# Sheet1.net
KiCad netlist of a schematic drawn in Altium Designer
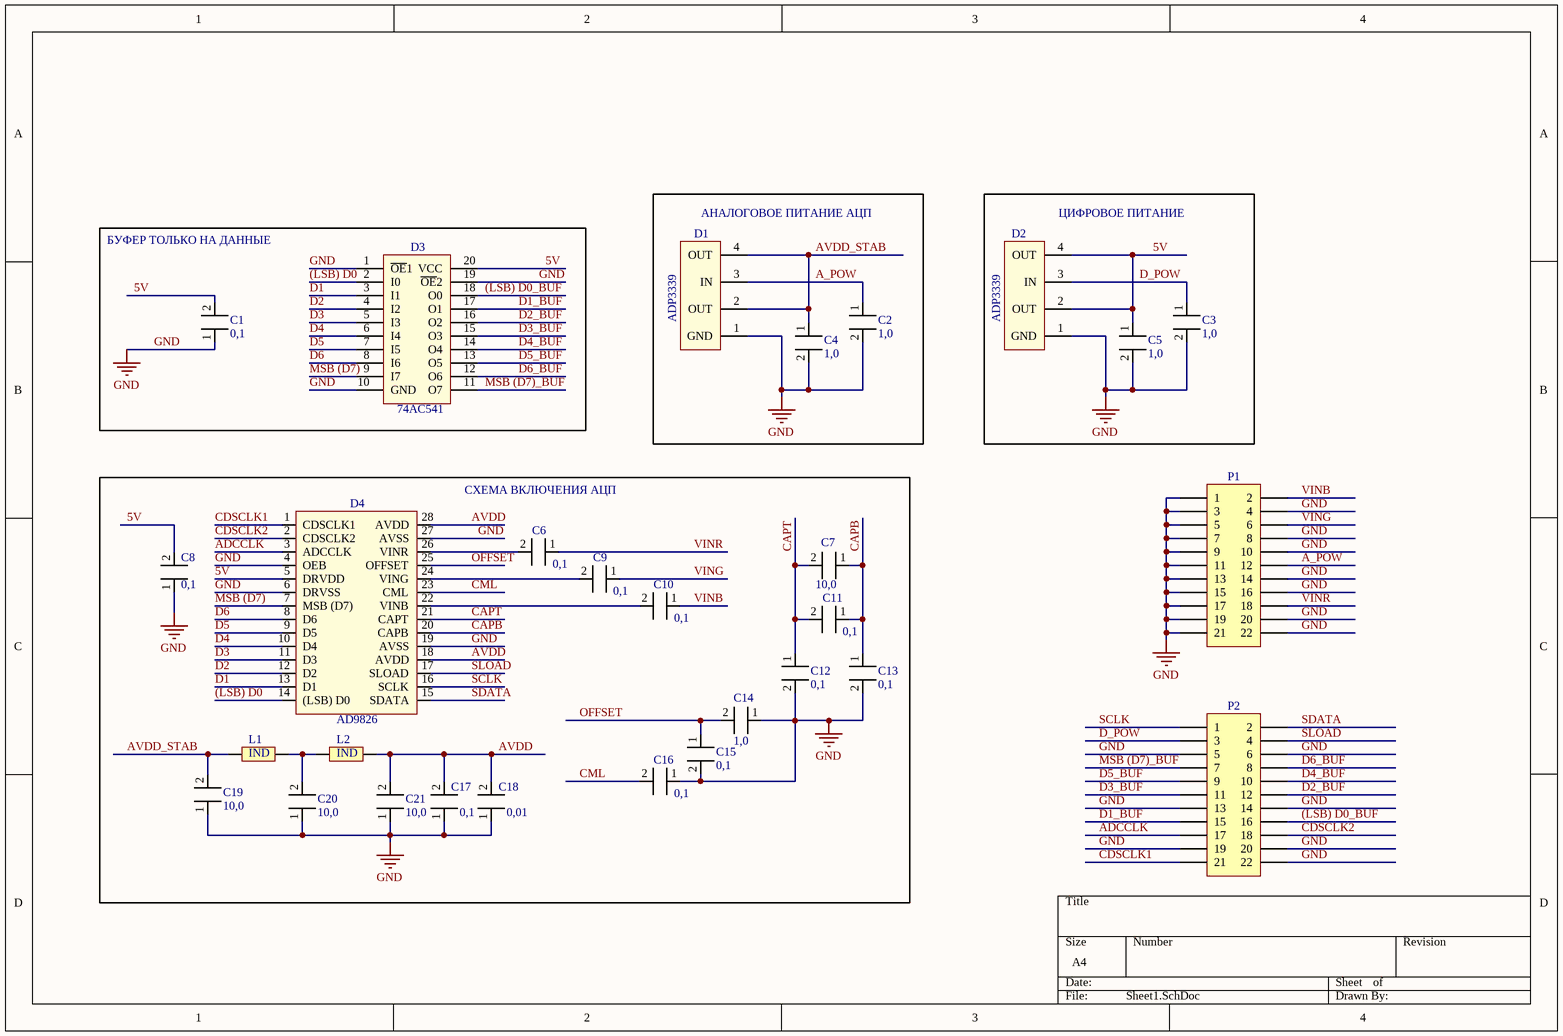
[diagram p0: Sheet1.SchDoc]

(export (version "E")
  (design (tool "Eeschema 10.0.6"))
  (components
    (comp (ref "C1") (value "0,1") (footprint "CAP_SMALL") (libsource (lib "Schlib") (part "CAP_SMALL")))
    (comp (ref "C2") (value "1,0") (footprint "CAP_SMALL") (libsource (lib "Schlib") (part "CAP_SMALL")))
    (comp (ref "C3") (value "1,0") (footprint "CAP_SMALL") (libsource (lib "Schlib") (part "CAP_SMALL")))
    (comp (ref "C4") (value "1,0") (footprint "CAP_SMALL") (libsource (lib "Schlib") (part "CAP_SMALL")))
    (comp (ref "C5") (value "1,0") (footprint "CAP_SMALL") (libsource (lib "Schlib") (part "CAP_SMALL")))
    (comp (ref "C6") (value "0,1") (footprint "CAP_SMALL") (libsource (lib "Schlib") (part "CAP_SMALL")))
    (comp (ref "C7") (value "10,0") (footprint "Cap_BIG") (libsource (lib "Schlib") (part "CAP_SMALL")))
    (comp (ref "C8") (value "0,1") (footprint "CAP_SMALL") (libsource (lib "Schlib") (part "CAP_SMALL")))
    (comp (ref "C9") (value "0,1") (footprint "CAP_SMALL") (libsource (lib "Schlib") (part "CAP_SMALL")))
    (comp (ref "C10") (value "0,1") (footprint "CAP_SMALL") (libsource (lib "Schlib") (part "CAP_SMALL")))
    (comp (ref "C11") (value "0,1") (footprint "CAP_SMALL") (libsource (lib "Schlib") (part "CAP_SMALL")))
    (comp (ref "C12") (value "0,1") (footprint "CAP_SMALL") (libsource (lib "Schlib") (part "CAP_SMALL")))
    (comp (ref "C13") (value "0,1") (footprint "CAP_SMALL") (libsource (lib "Schlib") (part "CAP_SMALL")))
    (comp (ref "C14") (value "1,0") (footprint "CAP_SMALL") (libsource (lib "Schlib") (part "CAP_SMALL")))
    (comp (ref "C15") (value "0,1") (footprint "CAP_SMALL") (libsource (lib "Schlib") (part "CAP_SMALL")))
    (comp (ref "C16") (value "0,1") (footprint "CAP_SMALL") (libsource (lib "Schlib") (part "CAP_SMALL")))
    (comp (ref "C17") (value "0,1") (footprint "CAP_SMALL") (libsource (lib "Schlib") (part "CAP_SMALL")))
    (comp (ref "C18") (value "0,01") (footprint "CAP_SMALL") (libsource (lib "Schlib") (part "CAP_SMALL")))
    (comp (ref "C19") (value "10,0") (footprint "Cap_BIG") (libsource (lib "Schlib") (part "CAP_SMALL")))
    (comp (ref "C20") (value "10,0") (footprint "Cap_BIG") (libsource (lib "Schlib") (part "CAP_SMALL")))
    (comp (ref "C21") (value "10,0") (footprint "Cap_BIG") (libsource (lib "Schlib") (part "CAP_SMALL")))
    (comp (ref "D1")
      (value "ADP3339")
      (footprint "SOT230P700X180-4N")
      (libsource (lib "Schlib") (part "ADP3339"))
    )
    (comp (ref "D2")
      (value "ADP3339")
      (footprint "SOT230P700X180-4N")
      (libsource (lib "Schlib") (part "ADP3339"))
    )
    (comp (ref "D3") (value "74AC541") (footprint "20S_M") (libsource (lib "Schlib") (part "74AC541")))
    (comp (ref "D4") (value "AD9826") (footprint "SSOP-28") (libsource (lib "Schlib") (part "AD9826")))
    (comp (ref "L1") (value "IND") (footprint "RES") (libsource (lib "Schlib") (part "RES")))
    (comp (ref "L2") (value "IND") (footprint "RES") (libsource (lib "Schlib") (part "RES")))
    (comp (ref "P1")
      (value "Header 11X2")
      (footprint "HDR2X11")
      (description "Header, 11-Pin, Dual row")
      (fields (field (name "PUBLISHER") "Altium Limited"))
      (libsource (lib "Miscellaneous Connectors") (part "Header 11X2"))
    )
    (comp (ref "P2")
      (value "Header 11X2")
      (footprint "HDR2X11")
      (description "Header, 11-Pin, Dual row")
      (fields (field (name "PUBLISHER") "Altium Limited"))
      (libsource (lib "Miscellaneous Connectors") (part "Header 11X2"))
    )
  )
  (nets
    (net (code "1") (name "/(LSB) D0") (class "Default")
      (node (ref "D3") (pin "2") (pinfunction "I0_2") (pintype "passive"))
      (node (ref "D4") (pin "14") (pinfunction "(LSB)_D0_14") (pintype "passive"))
    )
    (net (code "2") (name "/(LSB) D0_BUF") (class "Default")
      (node (ref "D3") (pin "18") (pinfunction "O0_18") (pintype "passive"))
      (node (ref "P2") (pin "16") (pinfunction "16_16") (pintype "passive"))
    )
    (net (code "3") (name "/5V") (class "Default")
      (node (ref "C1") (pin "2") (pinfunction "2_2") (pintype "passive"))
      (node (ref "C5") (pin "1") (pinfunction "1_1") (pintype "passive"))
      (node (ref "C8") (pin "2") (pinfunction "2_2") (pintype "passive"))
      (node (ref "D2") (pin "2") (pinfunction "OUT_2") (pintype "passive"))
      (node (ref "D2") (pin "4") (pinfunction "OUT_4") (pintype "passive"))
      (node (ref "D3") (pin "20") (pinfunction "VCC_20") (pintype "passive"))
      (node (ref "D4") (pin "5") (pinfunction "DRVDD_5") (pintype "passive"))
    )
    (net (code "4") (name "/ADCCLK") (class "Default")
      (node (ref "D4") (pin "3") (pinfunction "ADCCLK_3") (pintype "passive"))
      (node (ref "P2") (pin "17") (pinfunction "17_17") (pintype "passive"))
    )
    (net (code "5") (name "/AVDD") (class "Default")
      (node (ref "C17") (pin "2") (pinfunction "2_2") (pintype "passive"))
      (node (ref "C18") (pin "2") (pinfunction "2_2") (pintype "passive"))
      (node (ref "C21") (pin "2") (pinfunction "2_2") (pintype "passive"))
      (node (ref "D4") (pin "18") (pinfunction "AVDD_18") (pintype "passive"))
      (node (ref "D4") (pin "28") (pinfunction "AVDD_28") (pintype "passive"))
      (node (ref "L2") (pin "2") (pinfunction "2_2") (pintype "passive"))
    )
    (net (code "6") (name "/AVDD_STAB") (class "Default")
      (node (ref "C19") (pin "2") (pinfunction "2_2") (pintype "passive"))
      (node (ref "C4") (pin "1") (pinfunction "1_1") (pintype "passive"))
      (node (ref "D1") (pin "2") (pinfunction "OUT_2") (pintype "passive"))
      (node (ref "D1") (pin "4") (pinfunction "OUT_4") (pintype "passive"))
      (node (ref "L1") (pin "1") (pinfunction "1_1") (pintype "passive"))
    )
    (net (code "7") (name "/A_POW") (class "Default")
      (node (ref "C2") (pin "1") (pinfunction "1_1") (pintype "passive"))
      (node (ref "D1") (pin "3") (pinfunction "IN_3") (pintype "passive"))
      (node (ref "P1") (pin "12") (pinfunction "12_12") (pintype "passive"))
    )
    (net (code "8") (name "/CAPB") (class "Default")
      (node (ref "C11") (pin "1") (pinfunction "1_1") (pintype "passive"))
      (node (ref "C13") (pin "1") (pinfunction "1_1") (pintype "passive"))
      (node (ref "C7") (pin "1") (pinfunction "1_1") (pintype "passive"))
      (node (ref "D4") (pin "20") (pinfunction "CAPB_20") (pintype "passive"))
    )
    (net (code "9") (name "/CAPT") (class "Default")
      (node (ref "C11") (pin "2") (pinfunction "2_2") (pintype "passive"))
      (node (ref "C12") (pin "1") (pinfunction "1_1") (pintype "passive"))
      (node (ref "C7") (pin "2") (pinfunction "2_2") (pintype "passive"))
      (node (ref "D4") (pin "21") (pinfunction "CAPT_21") (pintype "passive"))
    )
    (net (code "10") (name "/CDSCLK1") (class "Default")
      (node (ref "D4") (pin "1") (pinfunction "CDSCLK1_1") (pintype "passive"))
      (node (ref "P2") (pin "21") (pinfunction "21_21") (pintype "passive"))
    )
    (net (code "11") (name "/CDSCLK2") (class "Default")
      (node (ref "D4") (pin "2") (pinfunction "CDSCLK2_2") (pintype "passive"))
      (node (ref "P2") (pin "18") (pinfunction "18_18") (pintype "passive"))
    )
    (net (code "12") (name "/CML") (class "Default")
      (node (ref "C16") (pin "2") (pinfunction "2_2") (pintype "passive"))
      (node (ref "D4") (pin "23") (pinfunction "CML_23") (pintype "passive"))
    )
    (net (code "13") (name "/D1") (class "Default")
      (node (ref "D3") (pin "3") (pinfunction "I1_3") (pintype "passive"))
      (node (ref "D4") (pin "13") (pinfunction "D1_13") (pintype "passive"))
    )
    (net (code "14") (name "/D1_BUF") (class "Default")
      (node (ref "D3") (pin "17") (pinfunction "O1_17") (pintype "passive"))
      (node (ref "P2") (pin "15") (pinfunction "15_15") (pintype "passive"))
    )
    (net (code "15") (name "/D2") (class "Default")
      (node (ref "D3") (pin "4") (pinfunction "I2_4") (pintype "passive"))
      (node (ref "D4") (pin "12") (pinfunction "D2_12") (pintype "passive"))
    )
    (net (code "16") (name "/D2_BUF") (class "Default")
      (node (ref "D3") (pin "16") (pinfunction "O2_16") (pintype "passive"))
      (node (ref "P2") (pin "12") (pinfunction "12_12") (pintype "passive"))
    )
    (net (code "17") (name "/D3") (class "Default")
      (node (ref "D3") (pin "5") (pinfunction "I3_5") (pintype "passive"))
      (node (ref "D4") (pin "11") (pinfunction "D3_11") (pintype "passive"))
    )
    (net (code "18") (name "/D3_BUF") (class "Default")
      (node (ref "D3") (pin "15") (pinfunction "O3_15") (pintype "passive"))
      (node (ref "P2") (pin "11") (pinfunction "11_11") (pintype "passive"))
    )
    (net (code "19") (name "/D4") (class "Default")
      (node (ref "D3") (pin "6") (pinfunction "I4_6") (pintype "passive"))
      (node (ref "D4") (pin "10") (pinfunction "D4_10") (pintype "passive"))
    )
    (net (code "20") (name "/D4_BUF") (class "Default")
      (node (ref "D3") (pin "14") (pinfunction "O4_14") (pintype "passive"))
      (node (ref "P2") (pin "10") (pinfunction "10_10") (pintype "passive"))
    )
    (net (code "21") (name "/D5") (class "Default")
      (node (ref "D3") (pin "7") (pinfunction "I5_7") (pintype "passive"))
      (node (ref "D4") (pin "9") (pinfunction "D5_9") (pintype "passive"))
    )
    (net (code "22") (name "/D5_BUF") (class "Default")
      (node (ref "D3") (pin "13") (pinfunction "O5_13") (pintype "passive"))
      (node (ref "P2") (pin "9") (pinfunction "9_9") (pintype "passive"))
    )
    (net (code "23") (name "/D6") (class "Default")
      (node (ref "D3") (pin "8") (pinfunction "I6_8") (pintype "passive"))
      (node (ref "D4") (pin "8") (pinfunction "D6_8") (pintype "passive"))
    )
    (net (code "24") (name "/D6_BUF") (class "Default")
      (node (ref "D3") (pin "12") (pinfunction "O6_12") (pintype "passive"))
      (node (ref "P2") (pin "8") (pinfunction "8_8") (pintype "passive"))
    )
    (net (code "25") (name "/D_POW") (class "Default")
      (node (ref "C3") (pin "1") (pinfunction "1_1") (pintype "passive"))
      (node (ref "D2") (pin "3") (pinfunction "IN_3") (pintype "passive"))
      (node (ref "P2") (pin "3") (pinfunction "3_3") (pintype "passive"))
    )
    (net (code "26") (name "/MSB (D7)") (class "Default")
      (node (ref "D3") (pin "9") (pinfunction "I7_9") (pintype "passive"))
      (node (ref "D4") (pin "7") (pinfunction "MSB_(D7)_7") (pintype "passive"))
    )
    (net (code "27") (name "/MSB (D7)_BUF") (class "Default")
      (node (ref "D3") (pin "11") (pinfunction "O7_11") (pintype "passive"))
      (node (ref "P2") (pin "7") (pinfunction "7_7") (pintype "passive"))
    )
    (net (code "28") (name "/OFFSET") (class "Default")
      (node (ref "C14") (pin "2") (pinfunction "2_2") (pintype "passive"))
      (node (ref "C15") (pin "1") (pinfunction "1_1") (pintype "passive"))
      (node (ref "D4") (pin "25") (pinfunction "OFFSET_25") (pintype "passive"))
    )
    (net (code "29") (name "/SCLK") (class "Default")
      (node (ref "D4") (pin "16") (pinfunction "SCLK_16") (pintype "passive"))
      (node (ref "P2") (pin "1") (pinfunction "1_1") (pintype "passive"))
    )
    (net (code "30") (name "/SDATA") (class "Default")
      (node (ref "D4") (pin "15") (pinfunction "SDATA_15") (pintype "passive"))
      (node (ref "P2") (pin "2") (pinfunction "2_2") (pintype "passive"))
    )
    (net (code "31") (name "/SLOAD") (class "Default")
      (node (ref "D4") (pin "17") (pinfunction "SLOAD_17") (pintype "passive"))
      (node (ref "P2") (pin "4") (pinfunction "4_4") (pintype "passive"))
    )
    (net (code "32") (name "/VINB") (class "Default")
      (node (ref "C10") (pin "1") (pinfunction "1_1") (pintype "passive"))
      (node (ref "P1") (pin "2") (pinfunction "2_2") (pintype "passive"))
    )
    (net (code "33") (name "/VING") (class "Default")
      (node (ref "C9") (pin "1") (pinfunction "1_1") (pintype "passive"))
      (node (ref "P1") (pin "6") (pinfunction "6_6") (pintype "passive"))
    )
    (net (code "34") (name "/VINR") (class "Default")
      (node (ref "C6") (pin "1") (pinfunction "1_1") (pintype "passive"))
      (node (ref "P1") (pin "18") (pinfunction "18_18") (pintype "passive"))
    )
    (net (code "35") (name "GND") (class "Default")
      (node (ref "C1") (pin "1") (pinfunction "1_1") (pintype "passive"))
      (node (ref "C12") (pin "2") (pinfunction "2_2") (pintype "passive"))
      (node (ref "C13") (pin "2") (pinfunction "2_2") (pintype "passive"))
      (node (ref "C14") (pin "1") (pinfunction "1_1") (pintype "passive"))
      (node (ref "C15") (pin "2") (pinfunction "2_2") (pintype "passive"))
      (node (ref "C16") (pin "1") (pinfunction "1_1") (pintype "passive"))
      (node (ref "C17") (pin "1") (pinfunction "1_1") (pintype "passive"))
      (node (ref "C18") (pin "1") (pinfunction "1_1") (pintype "passive"))
      (node (ref "C19") (pin "1") (pinfunction "1_1") (pintype "passive"))
      (node (ref "C2") (pin "2") (pinfunction "2_2") (pintype "passive"))
      (node (ref "C20") (pin "1") (pinfunction "1_1") (pintype "passive"))
      (node (ref "C21") (pin "1") (pinfunction "1_1") (pintype "passive"))
      (node (ref "C3") (pin "2") (pinfunction "2_2") (pintype "passive"))
      (node (ref "C4") (pin "2") (pinfunction "2_2") (pintype "passive"))
      (node (ref "C5") (pin "2") (pinfunction "2_2") (pintype "passive"))
      (node (ref "C8") (pin "1") (pinfunction "1_1") (pintype "passive"))
      (node (ref "D1") (pin "1") (pinfunction "GND_1") (pintype "passive"))
      (node (ref "D2") (pin "1") (pinfunction "GND_1") (pintype "passive"))
      (node (ref "D3") (pin "1") (pinfunction "~{OE}1_1") (pintype "passive"))
      (node (ref "D3") (pin "10") (pinfunction "GND_10") (pintype "passive"))
      (node (ref "D3") (pin "19") (pinfunction "~{OE}2_19") (pintype "passive"))
      (node (ref "D4") (pin "19") (pinfunction "AVSS_19") (pintype "passive"))
      (node (ref "D4") (pin "27") (pinfunction "AVSS_27") (pintype "passive"))
      (node (ref "D4") (pin "4") (pinfunction "OEB_4") (pintype "passive"))
      (node (ref "D4") (pin "6") (pinfunction "DRVSS_6") (pintype "passive"))
      (node (ref "P1") (pin "1") (pinfunction "1_1") (pintype "passive"))
      (node (ref "P1") (pin "10") (pinfunction "10_10") (pintype "passive"))
      (node (ref "P1") (pin "11") (pinfunction "11_11") (pintype "passive"))
      (node (ref "P1") (pin "13") (pinfunction "13_13") (pintype "passive"))
      (node (ref "P1") (pin "14") (pinfunction "14_14") (pintype "passive"))
      (node (ref "P1") (pin "15") (pinfunction "15_15") (pintype "passive"))
      (node (ref "P1") (pin "16") (pinfunction "16_16") (pintype "passive"))
      (node (ref "P1") (pin "17") (pinfunction "17_17") (pintype "passive"))
      (node (ref "P1") (pin "19") (pinfunction "19_19") (pintype "passive"))
      (node (ref "P1") (pin "20") (pinfunction "20_20") (pintype "passive"))
      (node (ref "P1") (pin "21") (pinfunction "21_21") (pintype "passive"))
      (node (ref "P1") (pin "22") (pinfunction "22_22") (pintype "passive"))
      (node (ref "P1") (pin "3") (pinfunction "3_3") (pintype "passive"))
      (node (ref "P1") (pin "4") (pinfunction "4_4") (pintype "passive"))
      (node (ref "P1") (pin "5") (pinfunction "5_5") (pintype "passive"))
      (node (ref "P1") (pin "7") (pinfunction "7_7") (pintype "passive"))
      (node (ref "P1") (pin "8") (pinfunction "8_8") (pintype "passive"))
      (node (ref "P1") (pin "9") (pinfunction "9_9") (pintype "passive"))
      (node (ref "P2") (pin "13") (pinfunction "13_13") (pintype "passive"))
      (node (ref "P2") (pin "14") (pinfunction "14_14") (pintype "passive"))
      (node (ref "P2") (pin "19") (pinfunction "19_19") (pintype "passive"))
      (node (ref "P2") (pin "20") (pinfunction "20_20") (pintype "passive"))
      (node (ref "P2") (pin "22") (pinfunction "22_22") (pintype "passive"))
      (node (ref "P2") (pin "5") (pinfunction "5_5") (pintype "passive"))
      (node (ref "P2") (pin "6") (pinfunction "6_6") (pintype "passive"))
    )
    (net (code "36") (name "Net-(C20-Pad2)") (class "Default")
      (node (ref "C20") (pin "2") (pinfunction "2_2") (pintype "passive"))
      (node (ref "L1") (pin "2") (pinfunction "2_2") (pintype "passive"))
      (node (ref "L2") (pin "1") (pinfunction "1_1") (pintype "passive"))
    )
    (net (code "37") (name "Net-(D4-VINB)") (class "Default")
      (node (ref "C10") (pin "2") (pinfunction "2_2") (pintype "passive"))
      (node (ref "D4") (pin "22") (pinfunction "VINB_22") (pintype "passive"))
    )
    (net (code "38") (name "Net-(D4-VING)") (class "Default")
      (node (ref "C9") (pin "2") (pinfunction "2_2") (pintype "passive"))
      (node (ref "D4") (pin "24") (pinfunction "VING_24") (pintype "passive"))
    )
    (net (code "39") (name "Net-(D4-VINR)") (class "Default")
      (node (ref "C6") (pin "2") (pinfunction "2_2") (pintype "passive"))
      (node (ref "D4") (pin "26") (pinfunction "VINR_26") (pintype "passive"))
    )
  )
)
